# PGTNX08_pitch_out.net
KiCad netlist of a schematic drawn in EAGLE
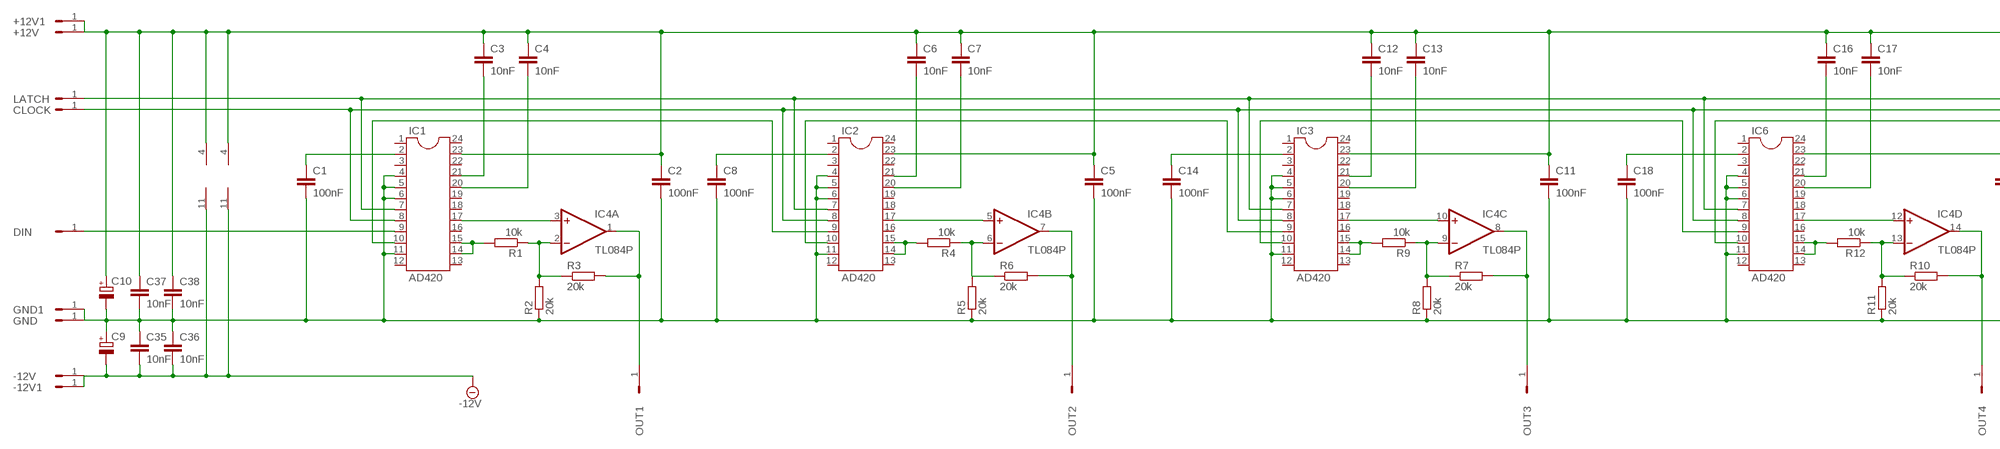
[diagram p0: schematic, sheet 1, part 1 of 2]
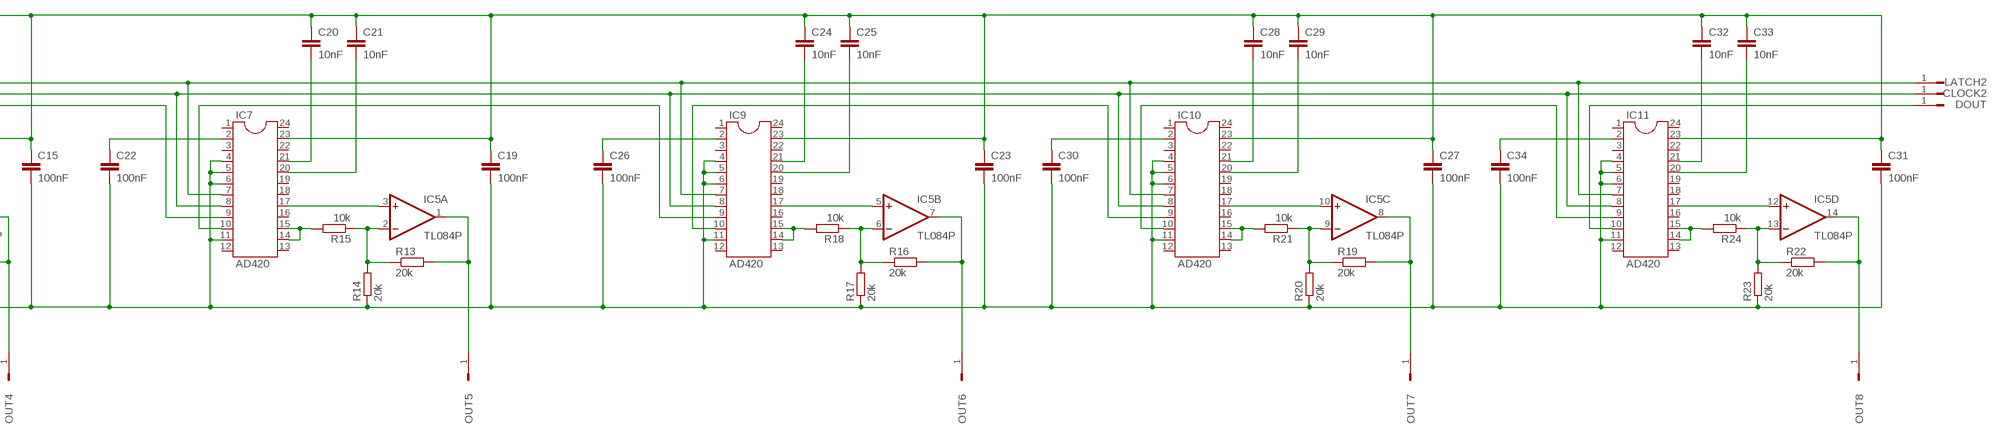
[diagram p1: schematic, sheet 1, part 2 of 2]

(export (version "E")
  (design (tool "Eeschema 10.0.6"))
  (components
    (comp (ref "+12V")
      (value "HEADER/MALE/01")
      (footprint "eagle-import:HEADER_MALE_01")
      (libsource (lib "eagle-import") (part "HEADER/MALE/01"))
    )
    (comp (ref "+12V1")
      (value "HEADER/MALE/01")
      (footprint "eagle-import:HEADER_MALE_01")
      (libsource (lib "eagle-import") (part "HEADER/MALE/01"))
    )
    (comp (ref "-12V")
      (value "HEADER/MALE/01")
      (footprint "eagle-import:HEADER_MALE_01")
      (libsource (lib "eagle-import") (part "HEADER/MALE/01"))
    )
    (comp (ref "-12V1")
      (value "HEADER/MALE/01")
      (footprint "eagle-import:HEADER_MALE_01")
      (libsource (lib "eagle-import") (part "HEADER/MALE/01"))
    )
    (comp (ref "C1")
      (value "100nF")
      (footprint "eagle-import:CERAMICDISC_5")
      (libsource (lib "eagle-import") (part "CAPACITORCERAMICDISC/5"))
    )
    (comp (ref "C2")
      (value "100nF")
      (footprint "eagle-import:CERAMICDISC_5")
      (libsource (lib "eagle-import") (part "CAPACITORCERAMICDISC/5"))
    )
    (comp (ref "C3")
      (value "10nF")
      (footprint "eagle-import:CERAMICDISC_5")
      (libsource (lib "eagle-import") (part "CAPACITORCERAMICDISC/5"))
    )
    (comp (ref "C4")
      (value "10nF")
      (footprint "eagle-import:CERAMICDISC_5")
      (libsource (lib "eagle-import") (part "CAPACITORCERAMICDISC/5"))
    )
    (comp (ref "C5")
      (value "100nF")
      (footprint "eagle-import:CERAMICDISC_5")
      (libsource (lib "eagle-import") (part "CAPACITORCERAMICDISC/5"))
    )
    (comp (ref "C6")
      (value "10nF")
      (footprint "eagle-import:CERAMICDISC_5")
      (libsource (lib "eagle-import") (part "CAPACITORCERAMICDISC/5"))
    )
    (comp (ref "C7")
      (value "10nF")
      (footprint "eagle-import:CERAMICDISC_5")
      (libsource (lib "eagle-import") (part "CAPACITORCERAMICDISC/5"))
    )
    (comp (ref "C8")
      (value "100nF")
      (footprint "eagle-import:CERAMICDISC_5")
      (libsource (lib "eagle-import") (part "CAPACITORCERAMICDISC/5"))
    )
    (comp (ref "C9")
      (value "CAPACITOR/POLARIZEDE2.5-6")
      (footprint "eagle-import:E2,5-6")
      (libsource (lib "eagle-import") (part "CAPACITOR/POLARIZEDE2.5-6"))
    )
    (comp (ref "C10")
      (value "CAPACITOR/POLARIZEDE2.5-6")
      (footprint "eagle-import:E2,5-6")
      (libsource (lib "eagle-import") (part "CAPACITOR/POLARIZEDE2.5-6"))
    )
    (comp (ref "C11")
      (value "100nF")
      (footprint "eagle-import:CERAMICDISC_5")
      (libsource (lib "eagle-import") (part "CAPACITORCERAMICDISC/5"))
    )
    (comp (ref "C12")
      (value "10nF")
      (footprint "eagle-import:CERAMICDISC_5")
      (libsource (lib "eagle-import") (part "CAPACITORCERAMICDISC/5"))
    )
    (comp (ref "C13")
      (value "10nF")
      (footprint "eagle-import:CERAMICDISC_5")
      (libsource (lib "eagle-import") (part "CAPACITORCERAMICDISC/5"))
    )
    (comp (ref "C14")
      (value "100nF")
      (footprint "eagle-import:CERAMICDISC_5")
      (libsource (lib "eagle-import") (part "CAPACITORCERAMICDISC/5"))
    )
    (comp (ref "C15")
      (value "100nF")
      (footprint "eagle-import:CERAMICDISC_5")
      (libsource (lib "eagle-import") (part "CAPACITORCERAMICDISC/5"))
    )
    (comp (ref "C16")
      (value "10nF")
      (footprint "eagle-import:CERAMICDISC_5")
      (libsource (lib "eagle-import") (part "CAPACITORCERAMICDISC/5"))
    )
    (comp (ref "C17")
      (value "10nF")
      (footprint "eagle-import:CERAMICDISC_5")
      (libsource (lib "eagle-import") (part "CAPACITORCERAMICDISC/5"))
    )
    (comp (ref "C18")
      (value "100nF")
      (footprint "eagle-import:CERAMICDISC_5")
      (libsource (lib "eagle-import") (part "CAPACITORCERAMICDISC/5"))
    )
    (comp (ref "C19")
      (value "100nF")
      (footprint "eagle-import:CERAMICDISC_5")
      (libsource (lib "eagle-import") (part "CAPACITORCERAMICDISC/5"))
    )
    (comp (ref "C20")
      (value "10nF")
      (footprint "eagle-import:CERAMICDISC_5")
      (libsource (lib "eagle-import") (part "CAPACITORCERAMICDISC/5"))
    )
    (comp (ref "C21")
      (value "10nF")
      (footprint "eagle-import:CERAMICDISC_5")
      (libsource (lib "eagle-import") (part "CAPACITORCERAMICDISC/5"))
    )
    (comp (ref "C22")
      (value "100nF")
      (footprint "eagle-import:CERAMICDISC_5")
      (libsource (lib "eagle-import") (part "CAPACITORCERAMICDISC/5"))
    )
    (comp (ref "C23")
      (value "100nF")
      (footprint "eagle-import:CERAMICDISC_5")
      (libsource (lib "eagle-import") (part "CAPACITORCERAMICDISC/5"))
    )
    (comp (ref "C24")
      (value "10nF")
      (footprint "eagle-import:CERAMICDISC_5")
      (libsource (lib "eagle-import") (part "CAPACITORCERAMICDISC/5"))
    )
    (comp (ref "C25")
      (value "10nF")
      (footprint "eagle-import:CERAMICDISC_5")
      (libsource (lib "eagle-import") (part "CAPACITORCERAMICDISC/5"))
    )
    (comp (ref "C26")
      (value "100nF")
      (footprint "eagle-import:CERAMICDISC_5")
      (libsource (lib "eagle-import") (part "CAPACITORCERAMICDISC/5"))
    )
    (comp (ref "C27")
      (value "100nF")
      (footprint "eagle-import:CERAMICDISC_5")
      (libsource (lib "eagle-import") (part "CAPACITORCERAMICDISC/5"))
    )
    (comp (ref "C28")
      (value "10nF")
      (footprint "eagle-import:CERAMICDISC_5")
      (libsource (lib "eagle-import") (part "CAPACITORCERAMICDISC/5"))
    )
    (comp (ref "C29")
      (value "10nF")
      (footprint "eagle-import:CERAMICDISC_5")
      (libsource (lib "eagle-import") (part "CAPACITORCERAMICDISC/5"))
    )
    (comp (ref "C30")
      (value "100nF")
      (footprint "eagle-import:CERAMICDISC_5")
      (libsource (lib "eagle-import") (part "CAPACITORCERAMICDISC/5"))
    )
    (comp (ref "C31")
      (value "100nF")
      (footprint "eagle-import:CERAMICDISC_5")
      (libsource (lib "eagle-import") (part "CAPACITORCERAMICDISC/5"))
    )
    (comp (ref "C32")
      (value "10nF")
      (footprint "eagle-import:CERAMICDISC_5")
      (libsource (lib "eagle-import") (part "CAPACITORCERAMICDISC/5"))
    )
    (comp (ref "C33")
      (value "10nF")
      (footprint "eagle-import:CERAMICDISC_5")
      (libsource (lib "eagle-import") (part "CAPACITORCERAMICDISC/5"))
    )
    (comp (ref "C34")
      (value "100nF")
      (footprint "eagle-import:CERAMICDISC_5")
      (libsource (lib "eagle-import") (part "CAPACITORCERAMICDISC/5"))
    )
    (comp (ref "C35")
      (value "10nF")
      (footprint "eagle-import:CERAMICDISC_5")
      (libsource (lib "eagle-import") (part "CAPACITORCERAMICDISC/5"))
    )
    (comp (ref "C36")
      (value "10nF")
      (footprint "eagle-import:CERAMICDISC_5")
      (libsource (lib "eagle-import") (part "CAPACITORCERAMICDISC/5"))
    )
    (comp (ref "C37")
      (value "10nF")
      (footprint "eagle-import:CERAMICDISC_5")
      (libsource (lib "eagle-import") (part "CAPACITORCERAMICDISC/5"))
    )
    (comp (ref "C38")
      (value "10nF")
      (footprint "eagle-import:CERAMICDISC_5")
      (libsource (lib "eagle-import") (part "CAPACITORCERAMICDISC/5"))
    )
    (comp (ref "CLOCK")
      (value "HEADER/MALE/01")
      (footprint "eagle-import:HEADER_MALE_01")
      (libsource (lib "eagle-import") (part "HEADER/MALE/01"))
    )
    (comp (ref "CLOCK2")
      (value "HEADER/MALE/01")
      (footprint "eagle-import:HEADER_MALE_01")
      (libsource (lib "eagle-import") (part "HEADER/MALE/01"))
    )
    (comp (ref "DIN")
      (value "HEADER/MALE/01")
      (footprint "eagle-import:HEADER_MALE_01")
      (libsource (lib "eagle-import") (part "HEADER/MALE/01"))
    )
    (comp (ref "DOUT")
      (value "HEADER/MALE/01")
      (footprint "eagle-import:HEADER_MALE_01")
      (libsource (lib "eagle-import") (part "HEADER/MALE/01"))
    )
    (comp (ref "GND")
      (value "HEADER/MALE/01")
      (footprint "eagle-import:HEADER_MALE_01")
      (libsource (lib "eagle-import") (part "HEADER/MALE/01"))
    )
    (comp (ref "GND1")
      (value "HEADER/MALE/01")
      (footprint "eagle-import:HEADER_MALE_01")
      (libsource (lib "eagle-import") (part "HEADER/MALE/01"))
    )
    (comp (ref "IC1")
      (value "AD420")
      (footprint "eagle-import:DIL24-3")
      (libsource (lib "eagle-import") (part "DIL24-3"))
    )
    (comp (ref "IC2")
      (value "AD420")
      (footprint "eagle-import:DIL24-3")
      (libsource (lib "eagle-import") (part "DIL24-3"))
    )
    (comp (ref "IC3")
      (value "AD420")
      (footprint "eagle-import:DIL24-3")
      (libsource (lib "eagle-import") (part "DIL24-3"))
    )
    (comp (ref "IC4")
      (value "TL084P")
      (footprint "eagle-import:DIL14")
      (libsource (lib "eagle-import") (part "TL084P"))
    )
    (comp (ref "IC5")
      (value "TL084P")
      (footprint "eagle-import:DIL14")
      (libsource (lib "eagle-import") (part "TL084P"))
    )
    (comp (ref "IC6")
      (value "AD420")
      (footprint "eagle-import:DIL24-3")
      (libsource (lib "eagle-import") (part "DIL24-3"))
    )
    (comp (ref "IC7")
      (value "AD420")
      (footprint "eagle-import:DIL24-3")
      (libsource (lib "eagle-import") (part "DIL24-3"))
    )
    (comp (ref "IC9")
      (value "AD420")
      (footprint "eagle-import:DIL24-3")
      (libsource (lib "eagle-import") (part "DIL24-3"))
    )
    (comp (ref "IC10")
      (value "AD420")
      (footprint "eagle-import:DIL24-3")
      (libsource (lib "eagle-import") (part "DIL24-3"))
    )
    (comp (ref "IC11")
      (value "AD420")
      (footprint "eagle-import:DIL24-3")
      (libsource (lib "eagle-import") (part "DIL24-3"))
    )
    (comp (ref "LATCH")
      (value "HEADER/MALE/01")
      (footprint "eagle-import:HEADER_MALE_01")
      (libsource (lib "eagle-import") (part "HEADER/MALE/01"))
    )
    (comp (ref "LATCH2")
      (value "HEADER/MALE/01")
      (footprint "eagle-import:HEADER_MALE_01")
      (libsource (lib "eagle-import") (part "HEADER/MALE/01"))
    )
    (comp (ref "OUT1")
      (value "HEADER/MALE/01")
      (footprint "eagle-import:HEADER_MALE_01")
      (libsource (lib "eagle-import") (part "HEADER/MALE/01"))
    )
    (comp (ref "OUT2")
      (value "HEADER/MALE/01")
      (footprint "eagle-import:HEADER_MALE_01")
      (libsource (lib "eagle-import") (part "HEADER/MALE/01"))
    )
    (comp (ref "OUT3")
      (value "HEADER/MALE/01")
      (footprint "eagle-import:HEADER_MALE_01")
      (libsource (lib "eagle-import") (part "HEADER/MALE/01"))
    )
    (comp (ref "OUT4")
      (value "HEADER/MALE/01")
      (footprint "eagle-import:HEADER_MALE_01")
      (libsource (lib "eagle-import") (part "HEADER/MALE/01"))
    )
    (comp (ref "OUT5")
      (value "HEADER/MALE/01")
      (footprint "eagle-import:HEADER_MALE_01")
      (libsource (lib "eagle-import") (part "HEADER/MALE/01"))
    )
    (comp (ref "OUT6")
      (value "HEADER/MALE/01")
      (footprint "eagle-import:HEADER_MALE_01")
      (libsource (lib "eagle-import") (part "HEADER/MALE/01"))
    )
    (comp (ref "OUT7")
      (value "HEADER/MALE/01")
      (footprint "eagle-import:HEADER_MALE_01")
      (libsource (lib "eagle-import") (part "HEADER/MALE/01"))
    )
    (comp (ref "OUT8")
      (value "HEADER/MALE/01")
      (footprint "eagle-import:HEADER_MALE_01")
      (libsource (lib "eagle-import") (part "HEADER/MALE/01"))
    )
    (comp (ref "R1")
      (value "10k")
      (footprint "eagle-import:0204_7")
      (libsource (lib "eagle-import") (part "R-EU_0204/7"))
    )
    (comp (ref "R2")
      (value "20k")
      (footprint "eagle-import:0204_7")
      (libsource (lib "eagle-import") (part "R-EU_0204/7"))
    )
    (comp (ref "R3")
      (value "20k")
      (footprint "eagle-import:RESISTOR_7.5")
      (libsource (lib "eagle-import") (part "RESISTORRESISTOR/UPRIGHT/7.5"))
    )
    (comp (ref "R4")
      (value "10k")
      (footprint "eagle-import:0204_7")
      (libsource (lib "eagle-import") (part "R-EU_0204/7"))
    )
    (comp (ref "R5")
      (value "20k")
      (footprint "eagle-import:0204_7")
      (libsource (lib "eagle-import") (part "R-EU_0204/7"))
    )
    (comp (ref "R6")
      (value "20k")
      (footprint "eagle-import:RESISTOR_7.5")
      (libsource (lib "eagle-import") (part "RESISTORRESISTOR/UPRIGHT/7.5"))
    )
    (comp (ref "R7")
      (value "20k")
      (footprint "eagle-import:RESISTOR_7.5")
      (libsource (lib "eagle-import") (part "RESISTORRESISTOR/UPRIGHT/7.5"))
    )
    (comp (ref "R8")
      (value "20k")
      (footprint "eagle-import:RESISTOR_7.5")
      (libsource (lib "eagle-import") (part "RESISTORRESISTOR/UPRIGHT/7.5"))
    )
    (comp (ref "R9")
      (value "10k")
      (footprint "eagle-import:RESISTOR_7.5")
      (libsource (lib "eagle-import") (part "RESISTORRESISTOR/UPRIGHT/7.5"))
    )
    (comp (ref "R10")
      (value "20k")
      (footprint "eagle-import:RESISTOR_7.5")
      (libsource (lib "eagle-import") (part "RESISTORRESISTOR/UPRIGHT/7.5"))
    )
    (comp (ref "R11")
      (value "20k")
      (footprint "eagle-import:RESISTOR_7.5")
      (libsource (lib "eagle-import") (part "RESISTORRESISTOR/UPRIGHT/7.5"))
    )
    (comp (ref "R12")
      (value "10k")
      (footprint "eagle-import:RESISTOR_7.5")
      (libsource (lib "eagle-import") (part "RESISTORRESISTOR/UPRIGHT/7.5"))
    )
    (comp (ref "R13")
      (value "20k")
      (footprint "eagle-import:RESISTOR_7.5")
      (libsource (lib "eagle-import") (part "RESISTORRESISTOR/UPRIGHT/7.5"))
    )
    (comp (ref "R14")
      (value "20k")
      (footprint "eagle-import:RESISTOR_7.5")
      (libsource (lib "eagle-import") (part "RESISTORRESISTOR/UPRIGHT/7.5"))
    )
    (comp (ref "R15")
      (value "10k")
      (footprint "eagle-import:RESISTOR_7.5")
      (libsource (lib "eagle-import") (part "RESISTORRESISTOR/UPRIGHT/7.5"))
    )
    (comp (ref "R16")
      (value "20k")
      (footprint "eagle-import:RESISTOR_7.5")
      (libsource (lib "eagle-import") (part "RESISTORRESISTOR/UPRIGHT/7.5"))
    )
    (comp (ref "R17")
      (value "20k")
      (footprint "eagle-import:RESISTOR_7.5")
      (libsource (lib "eagle-import") (part "RESISTORRESISTOR/UPRIGHT/7.5"))
    )
    (comp (ref "R18")
      (value "10k")
      (footprint "eagle-import:RESISTOR_7.5")
      (libsource (lib "eagle-import") (part "RESISTORRESISTOR/UPRIGHT/7.5"))
    )
    (comp (ref "R19")
      (value "20k")
      (footprint "eagle-import:RESISTOR_7.5")
      (libsource (lib "eagle-import") (part "RESISTORRESISTOR/UPRIGHT/7.5"))
    )
    (comp (ref "R20")
      (value "20k")
      (footprint "eagle-import:RESISTOR_7.5")
      (libsource (lib "eagle-import") (part "RESISTORRESISTOR/UPRIGHT/7.5"))
    )
    (comp (ref "R21")
      (value "10k")
      (footprint "eagle-import:RESISTOR_7.5")
      (libsource (lib "eagle-import") (part "RESISTORRESISTOR/UPRIGHT/7.5"))
    )
    (comp (ref "R22")
      (value "20k")
      (footprint "eagle-import:RESISTOR_7.5")
      (libsource (lib "eagle-import") (part "RESISTORRESISTOR/UPRIGHT/7.5"))
    )
    (comp (ref "R23")
      (value "20k")
      (footprint "eagle-import:RESISTOR_7.5")
      (libsource (lib "eagle-import") (part "RESISTORRESISTOR/UPRIGHT/7.5"))
    )
    (comp (ref "R24")
      (value "10k")
      (footprint "eagle-import:RESISTOR_7.5")
      (libsource (lib "eagle-import") (part "RESISTORRESISTOR/UPRIGHT/7.5"))
    )
  )
  (nets
    (net (code "1") (name "-12V") (class "Default")
      (node (ref "-12V") (pin "1") (pinfunction "3_1") (pintype "passive"))
      (node (ref "-12V1") (pin "1") (pinfunction "3_1") (pintype "passive"))
      (node (ref "C35") (pin "2") (pinfunction "2_2") (pintype "passive"))
      (node (ref "C36") (pin "2") (pinfunction "2_2") (pintype "passive"))
      (node (ref "C9") (pin "-") (pinfunction "-_-") (pintype "passive"))
      (node (ref "IC4") (pin "11") (pinfunction "V-_11") (pintype "power_in"))
      (node (ref "IC5") (pin "11") (pinfunction "V-_11") (pintype "power_in"))
    )
    (net (code "2") (name "Net-(+12V-3)") (class "Default")
      (node (ref "+12V") (pin "1") (pinfunction "3_1") (pintype "passive"))
      (node (ref "+12V1") (pin "1") (pinfunction "3_1") (pintype "passive"))
      (node (ref "C10") (pin "+") (pinfunction "+_+") (pintype "passive"))
      (node (ref "C11") (pin "1") (pinfunction "1_1") (pintype "passive"))
      (node (ref "C12") (pin "1") (pinfunction "1_1") (pintype "passive"))
      (node (ref "C13") (pin "1") (pinfunction "1_1") (pintype "passive"))
      (node (ref "C15") (pin "1") (pinfunction "1_1") (pintype "passive"))
      (node (ref "C16") (pin "1") (pinfunction "1_1") (pintype "passive"))
      (node (ref "C17") (pin "1") (pinfunction "1_1") (pintype "passive"))
      (node (ref "C19") (pin "1") (pinfunction "1_1") (pintype "passive"))
      (node (ref "C2") (pin "1") (pinfunction "1_1") (pintype "passive"))
      (node (ref "C20") (pin "1") (pinfunction "1_1") (pintype "passive"))
      (node (ref "C21") (pin "1") (pinfunction "1_1") (pintype "passive"))
      (node (ref "C23") (pin "1") (pinfunction "1_1") (pintype "passive"))
      (node (ref "C24") (pin "1") (pinfunction "1_1") (pintype "passive"))
      (node (ref "C25") (pin "1") (pinfunction "1_1") (pintype "passive"))
      (node (ref "C27") (pin "1") (pinfunction "1_1") (pintype "passive"))
      (node (ref "C28") (pin "1") (pinfunction "1_1") (pintype "passive"))
      (node (ref "C29") (pin "1") (pinfunction "1_1") (pintype "passive"))
      (node (ref "C3") (pin "1") (pinfunction "1_1") (pintype "passive"))
      (node (ref "C31") (pin "1") (pinfunction "1_1") (pintype "passive"))
      (node (ref "C32") (pin "1") (pinfunction "1_1") (pintype "passive"))
      (node (ref "C33") (pin "1") (pinfunction "1_1") (pintype "passive"))
      (node (ref "C37") (pin "1") (pinfunction "1_1") (pintype "passive"))
      (node (ref "C38") (pin "1") (pinfunction "1_1") (pintype "passive"))
      (node (ref "C4") (pin "1") (pinfunction "1_1") (pintype "passive"))
      (node (ref "C5") (pin "1") (pinfunction "1_1") (pintype "passive"))
      (node (ref "C6") (pin "1") (pinfunction "1_1") (pintype "passive"))
      (node (ref "C7") (pin "1") (pinfunction "1_1") (pintype "passive"))
      (node (ref "IC1") (pin "23") (pinfunction "23_23") (pintype "passive"))
      (node (ref "IC10") (pin "23") (pinfunction "23_23") (pintype "passive"))
      (node (ref "IC11") (pin "23") (pinfunction "23_23") (pintype "passive"))
      (node (ref "IC2") (pin "23") (pinfunction "23_23") (pintype "passive"))
      (node (ref "IC3") (pin "23") (pinfunction "23_23") (pintype "passive"))
      (node (ref "IC4") (pin "4") (pinfunction "V+_4") (pintype "power_in"))
      (node (ref "IC5") (pin "4") (pinfunction "V+_4") (pintype "power_in"))
      (node (ref "IC6") (pin "23") (pinfunction "23_23") (pintype "passive"))
      (node (ref "IC7") (pin "23") (pinfunction "23_23") (pintype "passive"))
      (node (ref "IC9") (pin "23") (pinfunction "23_23") (pintype "passive"))
    )
    (net (code "3") (name "Net-(C1-Pad1)") (class "Default")
      (node (ref "C1") (pin "1") (pinfunction "1_1") (pintype "passive"))
      (node (ref "IC1") (pin "2") (pinfunction "2_2") (pintype "passive"))
    )
    (net (code "4") (name "Net-(C3-Pad2)") (class "Default")
      (node (ref "C3") (pin "2") (pinfunction "2_2") (pintype "passive"))
      (node (ref "IC1") (pin "21") (pinfunction "21_21") (pintype "passive"))
    )
    (net (code "5") (name "Net-(C4-Pad2)") (class "Default")
      (node (ref "C4") (pin "2") (pinfunction "2_2") (pintype "passive"))
      (node (ref "IC1") (pin "20") (pinfunction "20_20") (pintype "passive"))
    )
    (net (code "6") (name "Net-(C6-Pad2)") (class "Default")
      (node (ref "C6") (pin "2") (pinfunction "2_2") (pintype "passive"))
      (node (ref "IC2") (pin "21") (pinfunction "21_21") (pintype "passive"))
    )
    (net (code "7") (name "Net-(C7-Pad2)") (class "Default")
      (node (ref "C7") (pin "2") (pinfunction "2_2") (pintype "passive"))
      (node (ref "IC2") (pin "20") (pinfunction "20_20") (pintype "passive"))
    )
    (net (code "8") (name "Net-(C8-Pad1)") (class "Default")
      (node (ref "C8") (pin "1") (pinfunction "1_1") (pintype "passive"))
      (node (ref "IC2") (pin "2") (pinfunction "2_2") (pintype "passive"))
    )
    (net (code "9") (name "Net-(C12-Pad2)") (class "Default")
      (node (ref "C12") (pin "2") (pinfunction "2_2") (pintype "passive"))
      (node (ref "IC3") (pin "21") (pinfunction "21_21") (pintype "passive"))
    )
    (net (code "10") (name "Net-(C13-Pad2)") (class "Default")
      (node (ref "C13") (pin "2") (pinfunction "2_2") (pintype "passive"))
      (node (ref "IC3") (pin "20") (pinfunction "20_20") (pintype "passive"))
    )
    (net (code "11") (name "Net-(C14-Pad1)") (class "Default")
      (node (ref "C14") (pin "1") (pinfunction "1_1") (pintype "passive"))
      (node (ref "IC3") (pin "2") (pinfunction "2_2") (pintype "passive"))
    )
    (net (code "12") (name "Net-(C16-Pad2)") (class "Default")
      (node (ref "C16") (pin "2") (pinfunction "2_2") (pintype "passive"))
      (node (ref "IC6") (pin "21") (pinfunction "21_21") (pintype "passive"))
    )
    (net (code "13") (name "Net-(C17-Pad2)") (class "Default")
      (node (ref "C17") (pin "2") (pinfunction "2_2") (pintype "passive"))
      (node (ref "IC6") (pin "20") (pinfunction "20_20") (pintype "passive"))
    )
    (net (code "14") (name "Net-(C18-Pad1)") (class "Default")
      (node (ref "C18") (pin "1") (pinfunction "1_1") (pintype "passive"))
      (node (ref "IC6") (pin "2") (pinfunction "2_2") (pintype "passive"))
    )
    (net (code "15") (name "Net-(C20-Pad2)") (class "Default")
      (node (ref "C20") (pin "2") (pinfunction "2_2") (pintype "passive"))
      (node (ref "IC7") (pin "21") (pinfunction "21_21") (pintype "passive"))
    )
    (net (code "16") (name "Net-(C21-Pad2)") (class "Default")
      (node (ref "C21") (pin "2") (pinfunction "2_2") (pintype "passive"))
      (node (ref "IC7") (pin "20") (pinfunction "20_20") (pintype "passive"))
    )
    (net (code "17") (name "Net-(C22-Pad1)") (class "Default")
      (node (ref "C22") (pin "1") (pinfunction "1_1") (pintype "passive"))
      (node (ref "IC7") (pin "2") (pinfunction "2_2") (pintype "passive"))
    )
    (net (code "18") (name "Net-(C24-Pad2)") (class "Default")
      (node (ref "C24") (pin "2") (pinfunction "2_2") (pintype "passive"))
      (node (ref "IC9") (pin "21") (pinfunction "21_21") (pintype "passive"))
    )
    (net (code "19") (name "Net-(C25-Pad2)") (class "Default")
      (node (ref "C25") (pin "2") (pinfunction "2_2") (pintype "passive"))
      (node (ref "IC9") (pin "20") (pinfunction "20_20") (pintype "passive"))
    )
    (net (code "20") (name "Net-(C26-Pad1)") (class "Default")
      (node (ref "C26") (pin "1") (pinfunction "1_1") (pintype "passive"))
      (node (ref "IC9") (pin "2") (pinfunction "2_2") (pintype "passive"))
    )
    (net (code "21") (name "Net-(C28-Pad2)") (class "Default")
      (node (ref "C28") (pin "2") (pinfunction "2_2") (pintype "passive"))
      (node (ref "IC10") (pin "21") (pinfunction "21_21") (pintype "passive"))
    )
    (net (code "22") (name "Net-(C29-Pad2)") (class "Default")
      (node (ref "C29") (pin "2") (pinfunction "2_2") (pintype "passive"))
      (node (ref "IC10") (pin "20") (pinfunction "20_20") (pintype "passive"))
    )
    (net (code "23") (name "Net-(C30-Pad1)") (class "Default")
      (node (ref "C30") (pin "1") (pinfunction "1_1") (pintype "passive"))
      (node (ref "IC10") (pin "2") (pinfunction "2_2") (pintype "passive"))
    )
    (net (code "24") (name "Net-(C32-Pad2)") (class "Default")
      (node (ref "C32") (pin "2") (pinfunction "2_2") (pintype "passive"))
      (node (ref "IC11") (pin "21") (pinfunction "21_21") (pintype "passive"))
    )
    (net (code "25") (name "Net-(C33-Pad2)") (class "Default")
      (node (ref "C33") (pin "2") (pinfunction "2_2") (pintype "passive"))
      (node (ref "IC11") (pin "20") (pinfunction "20_20") (pintype "passive"))
    )
    (net (code "26") (name "Net-(C34-Pad1)") (class "Default")
      (node (ref "C34") (pin "1") (pinfunction "1_1") (pintype "passive"))
      (node (ref "IC11") (pin "2") (pinfunction "2_2") (pintype "passive"))
    )
    (net (code "27") (name "Net-(CLOCK-3)") (class "Default")
      (node (ref "CLOCK") (pin "1") (pinfunction "3_1") (pintype "passive"))
      (node (ref "CLOCK2") (pin "1") (pinfunction "3_1") (pintype "passive"))
      (node (ref "IC1") (pin "8") (pinfunction "8_8") (pintype "passive"))
      (node (ref "IC10") (pin "8") (pinfunction "8_8") (pintype "passive"))
      (node (ref "IC11") (pin "8") (pinfunction "8_8") (pintype "passive"))
      (node (ref "IC2") (pin "8") (pinfunction "8_8") (pintype "passive"))
      (node (ref "IC3") (pin "8") (pinfunction "8_8") (pintype "passive"))
      (node (ref "IC6") (pin "8") (pinfunction "8_8") (pintype "passive"))
      (node (ref "IC7") (pin "8") (pinfunction "8_8") (pintype "passive"))
      (node (ref "IC9") (pin "8") (pinfunction "8_8") (pintype "passive"))
    )
    (net (code "28") (name "Net-(DIN-3)") (class "Default")
      (node (ref "DIN") (pin "1") (pinfunction "3_1") (pintype "passive"))
      (node (ref "IC1") (pin "9") (pinfunction "9_9") (pintype "passive"))
    )
    (net (code "29") (name "Net-(DOUT-3)") (class "Default")
      (node (ref "DOUT") (pin "1") (pinfunction "3_1") (pintype "passive"))
      (node (ref "IC11") (pin "10") (pinfunction "10_10") (pintype "passive"))
    )
    (net (code "30") (name "Net-(GND-3)") (class "Default")
      (node (ref "C1") (pin "2") (pinfunction "2_2") (pintype "passive"))
      (node (ref "C10") (pin "-") (pinfunction "-_-") (pintype "passive"))
      (node (ref "C11") (pin "2") (pinfunction "2_2") (pintype "passive"))
      (node (ref "C14") (pin "2") (pinfunction "2_2") (pintype "passive"))
      (node (ref "C15") (pin "2") (pinfunction "2_2") (pintype "passive"))
      (node (ref "C18") (pin "2") (pinfunction "2_2") (pintype "passive"))
      (node (ref "C19") (pin "2") (pinfunction "2_2") (pintype "passive"))
      (node (ref "C2") (pin "2") (pinfunction "2_2") (pintype "passive"))
      (node (ref "C22") (pin "2") (pinfunction "2_2") (pintype "passive"))
      (node (ref "C23") (pin "2") (pinfunction "2_2") (pintype "passive"))
      (node (ref "C26") (pin "2") (pinfunction "2_2") (pintype "passive"))
      (node (ref "C27") (pin "2") (pinfunction "2_2") (pintype "passive"))
      (node (ref "C30") (pin "2") (pinfunction "2_2") (pintype "passive"))
      (node (ref "C31") (pin "2") (pinfunction "2_2") (pintype "passive"))
      (node (ref "C34") (pin "2") (pinfunction "2_2") (pintype "passive"))
      (node (ref "C35") (pin "1") (pinfunction "1_1") (pintype "passive"))
      (node (ref "C36") (pin "1") (pinfunction "1_1") (pintype "passive"))
      (node (ref "C37") (pin "2") (pinfunction "2_2") (pintype "passive"))
      (node (ref "C38") (pin "2") (pinfunction "2_2") (pintype "passive"))
      (node (ref "C5") (pin "2") (pinfunction "2_2") (pintype "passive"))
      (node (ref "C8") (pin "2") (pinfunction "2_2") (pintype "passive"))
      (node (ref "C9") (pin "+") (pinfunction "+_+") (pintype "passive"))
      (node (ref "GND") (pin "1") (pinfunction "3_1") (pintype "passive"))
      (node (ref "GND1") (pin "1") (pinfunction "3_1") (pintype "passive"))
      (node (ref "IC1") (pin "11") (pinfunction "11_11") (pintype "passive"))
      (node (ref "IC1") (pin "4") (pinfunction "4_4") (pintype "passive"))
      (node (ref "IC1") (pin "5") (pinfunction "5_5") (pintype "passive"))
      (node (ref "IC1") (pin "6") (pinfunction "6_6") (pintype "passive"))
      (node (ref "IC10") (pin "11") (pinfunction "11_11") (pintype "passive"))
      (node (ref "IC10") (pin "4") (pinfunction "4_4") (pintype "passive"))
      (node (ref "IC10") (pin "5") (pinfunction "5_5") (pintype "passive"))
      (node (ref "IC10") (pin "6") (pinfunction "6_6") (pintype "passive"))
      (node (ref "IC11") (pin "11") (pinfunction "11_11") (pintype "passive"))
      (node (ref "IC11") (pin "4") (pinfunction "4_4") (pintype "passive"))
      (node (ref "IC11") (pin "5") (pinfunction "5_5") (pintype "passive"))
      (node (ref "IC11") (pin "6") (pinfunction "6_6") (pintype "passive"))
      (node (ref "IC2") (pin "11") (pinfunction "11_11") (pintype "passive"))
      (node (ref "IC2") (pin "4") (pinfunction "4_4") (pintype "passive"))
      (node (ref "IC2") (pin "5") (pinfunction "5_5") (pintype "passive"))
      (node (ref "IC2") (pin "6") (pinfunction "6_6") (pintype "passive"))
      (node (ref "IC3") (pin "11") (pinfunction "11_11") (pintype "passive"))
      (node (ref "IC3") (pin "4") (pinfunction "4_4") (pintype "passive"))
      (node (ref "IC3") (pin "5") (pinfunction "5_5") (pintype "passive"))
      (node (ref "IC3") (pin "6") (pinfunction "6_6") (pintype "passive"))
      (node (ref "IC6") (pin "11") (pinfunction "11_11") (pintype "passive"))
      (node (ref "IC6") (pin "4") (pinfunction "4_4") (pintype "passive"))
      (node (ref "IC6") (pin "5") (pinfunction "5_5") (pintype "passive"))
      (node (ref "IC6") (pin "6") (pinfunction "6_6") (pintype "passive"))
      (node (ref "IC7") (pin "11") (pinfunction "11_11") (pintype "passive"))
      (node (ref "IC7") (pin "4") (pinfunction "4_4") (pintype "passive"))
      (node (ref "IC7") (pin "5") (pinfunction "5_5") (pintype "passive"))
      (node (ref "IC7") (pin "6") (pinfunction "6_6") (pintype "passive"))
      (node (ref "IC9") (pin "11") (pinfunction "11_11") (pintype "passive"))
      (node (ref "IC9") (pin "4") (pinfunction "4_4") (pintype "passive"))
      (node (ref "IC9") (pin "5") (pinfunction "5_5") (pintype "passive"))
      (node (ref "IC9") (pin "6") (pinfunction "6_6") (pintype "passive"))
      (node (ref "R11") (pin "1") (pinfunction "1_1") (pintype "passive"))
      (node (ref "R14") (pin "1") (pinfunction "1_1") (pintype "passive"))
      (node (ref "R17") (pin "1") (pinfunction "1_1") (pintype "passive"))
      (node (ref "R2") (pin "1") (pinfunction "1_1") (pintype "passive"))
      (node (ref "R20") (pin "1") (pinfunction "1_1") (pintype "passive"))
      (node (ref "R23") (pin "1") (pinfunction "1_1") (pintype "passive"))
      (node (ref "R5") (pin "1") (pinfunction "1_1") (pintype "passive"))
      (node (ref "R8") (pin "1") (pinfunction "1_1") (pintype "passive"))
    )
    (net (code "31") (name "Net-(IC1-Pad10)") (class "Default")
      (node (ref "IC1") (pin "10") (pinfunction "10_10") (pintype "passive"))
      (node (ref "IC2") (pin "9") (pinfunction "9_9") (pintype "passive"))
    )
    (net (code "32") (name "Net-(IC1-Pad14)") (class "Default")
      (node (ref "IC1") (pin "14") (pinfunction "14_14") (pintype "passive"))
      (node (ref "IC1") (pin "15") (pinfunction "15_15") (pintype "passive"))
      (node (ref "R1") (pin "2") (pinfunction "2_2") (pintype "passive"))
    )
    (net (code "33") (name "Net-(IC2-Pad10)") (class "Default")
      (node (ref "IC2") (pin "10") (pinfunction "10_10") (pintype "passive"))
      (node (ref "IC3") (pin "9") (pinfunction "9_9") (pintype "passive"))
    )
    (net (code "34") (name "Net-(IC2-Pad14)") (class "Default")
      (node (ref "IC2") (pin "14") (pinfunction "14_14") (pintype "passive"))
      (node (ref "IC2") (pin "15") (pinfunction "15_15") (pintype "passive"))
      (node (ref "R4") (pin "2") (pinfunction "2_2") (pintype "passive"))
    )
    (net (code "35") (name "Net-(IC3-Pad10)") (class "Default")
      (node (ref "IC3") (pin "10") (pinfunction "10_10") (pintype "passive"))
      (node (ref "IC6") (pin "9") (pinfunction "9_9") (pintype "passive"))
    )
    (net (code "36") (name "Net-(IC3-Pad14)") (class "Default")
      (node (ref "IC3") (pin "14") (pinfunction "14_14") (pintype "passive"))
      (node (ref "IC3") (pin "15") (pinfunction "15_15") (pintype "passive"))
      (node (ref "R9") (pin "2") (pinfunction "2_2") (pintype "passive"))
    )
    (net (code "37") (name "Net-(IC4A-+IN)") (class "Default")
      (node (ref "IC1") (pin "17") (pinfunction "17_17") (pintype "passive"))
      (node (ref "IC4") (pin "3") (pinfunction "+IN_3") (pintype "input"))
    )
    (net (code "38") (name "Net-(IC4A--IN)") (class "Default")
      (node (ref "IC4") (pin "2") (pinfunction "-IN_2") (pintype "input"))
      (node (ref "R1") (pin "1") (pinfunction "1_1") (pintype "passive"))
      (node (ref "R2") (pin "2") (pinfunction "2_2") (pintype "passive"))
      (node (ref "R3") (pin "1") (pinfunction "1_1") (pintype "passive"))
    )
    (net (code "39") (name "Net-(IC4A-OUT)") (class "Default")
      (node (ref "IC4") (pin "1") (pinfunction "OUT_1") (pintype "output"))
      (node (ref "OUT1") (pin "1") (pinfunction "3_1") (pintype "passive"))
      (node (ref "R3") (pin "2") (pinfunction "2_2") (pintype "passive"))
    )
    (net (code "40") (name "Net-(IC4B-+IN)") (class "Default")
      (node (ref "IC2") (pin "17") (pinfunction "17_17") (pintype "passive"))
      (node (ref "IC4") (pin "5") (pinfunction "+IN_5") (pintype "input"))
    )
    (net (code "41") (name "Net-(IC4B--IN)") (class "Default")
      (node (ref "IC4") (pin "6") (pinfunction "-IN_6") (pintype "input"))
      (node (ref "R4") (pin "1") (pinfunction "1_1") (pintype "passive"))
      (node (ref "R5") (pin "2") (pinfunction "2_2") (pintype "passive"))
      (node (ref "R6") (pin "1") (pinfunction "1_1") (pintype "passive"))
    )
    (net (code "42") (name "Net-(IC4B-OUT)") (class "Default")
      (node (ref "IC4") (pin "7") (pinfunction "OUT_7") (pintype "output"))
      (node (ref "OUT2") (pin "1") (pinfunction "3_1") (pintype "passive"))
      (node (ref "R6") (pin "2") (pinfunction "2_2") (pintype "passive"))
    )
    (net (code "43") (name "Net-(IC4C-+IN)") (class "Default")
      (node (ref "IC3") (pin "17") (pinfunction "17_17") (pintype "passive"))
      (node (ref "IC4") (pin "10") (pinfunction "+IN_10") (pintype "input"))
    )
    (net (code "44") (name "Net-(IC4C--IN)") (class "Default")
      (node (ref "IC4") (pin "9") (pinfunction "-IN_9") (pintype "input"))
      (node (ref "R7") (pin "1") (pinfunction "1_1") (pintype "passive"))
      (node (ref "R8") (pin "2") (pinfunction "2_2") (pintype "passive"))
      (node (ref "R9") (pin "1") (pinfunction "1_1") (pintype "passive"))
    )
    (net (code "45") (name "Net-(IC4C-OUT)") (class "Default")
      (node (ref "IC4") (pin "8") (pinfunction "OUT_8") (pintype "output"))
      (node (ref "OUT3") (pin "1") (pinfunction "3_1") (pintype "passive"))
      (node (ref "R7") (pin "2") (pinfunction "2_2") (pintype "passive"))
    )
    (net (code "46") (name "Net-(IC4D-+IN)") (class "Default")
      (node (ref "IC4") (pin "12") (pinfunction "+IN_12") (pintype "input"))
      (node (ref "IC6") (pin "17") (pinfunction "17_17") (pintype "passive"))
    )
    (net (code "47") (name "Net-(IC4D--IN)") (class "Default")
      (node (ref "IC4") (pin "13") (pinfunction "-IN_13") (pintype "input"))
      (node (ref "R10") (pin "1") (pinfunction "1_1") (pintype "passive"))
      (node (ref "R11") (pin "2") (pinfunction "2_2") (pintype "passive"))
      (node (ref "R12") (pin "1") (pinfunction "1_1") (pintype "passive"))
    )
    (net (code "48") (name "Net-(IC4D-OUT)") (class "Default")
      (node (ref "IC4") (pin "14") (pinfunction "OUT_14") (pintype "output"))
      (node (ref "OUT4") (pin "1") (pinfunction "3_1") (pintype "passive"))
      (node (ref "R10") (pin "2") (pinfunction "2_2") (pintype "passive"))
    )
    (net (code "49") (name "Net-(IC5A-+IN)") (class "Default")
      (node (ref "IC5") (pin "3") (pinfunction "+IN_3") (pintype "input"))
      (node (ref "IC7") (pin "17") (pinfunction "17_17") (pintype "passive"))
    )
    (net (code "50") (name "Net-(IC5A--IN)") (class "Default")
      (node (ref "IC5") (pin "2") (pinfunction "-IN_2") (pintype "input"))
      (node (ref "R13") (pin "1") (pinfunction "1_1") (pintype "passive"))
      (node (ref "R14") (pin "2") (pinfunction "2_2") (pintype "passive"))
      (node (ref "R15") (pin "1") (pinfunction "1_1") (pintype "passive"))
    )
    (net (code "51") (name "Net-(IC5A-OUT)") (class "Default")
      (node (ref "IC5") (pin "1") (pinfunction "OUT_1") (pintype "output"))
      (node (ref "OUT5") (pin "1") (pinfunction "3_1") (pintype "passive"))
      (node (ref "R13") (pin "2") (pinfunction "2_2") (pintype "passive"))
    )
    (net (code "52") (name "Net-(IC5B-+IN)") (class "Default")
      (node (ref "IC5") (pin "5") (pinfunction "+IN_5") (pintype "input"))
      (node (ref "IC9") (pin "17") (pinfunction "17_17") (pintype "passive"))
    )
    (net (code "53") (name "Net-(IC5B--IN)") (class "Default")
      (node (ref "IC5") (pin "6") (pinfunction "-IN_6") (pintype "input"))
      (node (ref "R16") (pin "1") (pinfunction "1_1") (pintype "passive"))
      (node (ref "R17") (pin "2") (pinfunction "2_2") (pintype "passive"))
      (node (ref "R18") (pin "1") (pinfunction "1_1") (pintype "passive"))
    )
    (net (code "54") (name "Net-(IC5B-OUT)") (class "Default")
      (node (ref "IC5") (pin "7") (pinfunction "OUT_7") (pintype "output"))
      (node (ref "OUT6") (pin "1") (pinfunction "3_1") (pintype "passive"))
      (node (ref "R16") (pin "2") (pinfunction "2_2") (pintype "passive"))
    )
    (net (code "55") (name "Net-(IC5C-+IN)") (class "Default")
      (node (ref "IC10") (pin "17") (pinfunction "17_17") (pintype "passive"))
      (node (ref "IC5") (pin "10") (pinfunction "+IN_10") (pintype "input"))
    )
    (net (code "56") (name "Net-(IC5C--IN)") (class "Default")
      (node (ref "IC5") (pin "9") (pinfunction "-IN_9") (pintype "input"))
      (node (ref "R19") (pin "1") (pinfunction "1_1") (pintype "passive"))
      (node (ref "R20") (pin "2") (pinfunction "2_2") (pintype "passive"))
      (node (ref "R21") (pin "1") (pinfunction "1_1") (pintype "passive"))
    )
    (net (code "57") (name "Net-(IC5C-OUT)") (class "Default")
      (node (ref "IC5") (pin "8") (pinfunction "OUT_8") (pintype "output"))
      (node (ref "OUT7") (pin "1") (pinfunction "3_1") (pintype "passive"))
      (node (ref "R19") (pin "2") (pinfunction "2_2") (pintype "passive"))
    )
    (net (code "58") (name "Net-(IC5D-+IN)") (class "Default")
      (node (ref "IC11") (pin "17") (pinfunction "17_17") (pintype "passive"))
      (node (ref "IC5") (pin "12") (pinfunction "+IN_12") (pintype "input"))
    )
    (net (code "59") (name "Net-(IC5D--IN)") (class "Default")
      (node (ref "IC5") (pin "13") (pinfunction "-IN_13") (pintype "input"))
      (node (ref "R22") (pin "1") (pinfunction "1_1") (pintype "passive"))
      (node (ref "R23") (pin "2") (pinfunction "2_2") (pintype "passive"))
      (node (ref "R24") (pin "1") (pinfunction "1_1") (pintype "passive"))
    )
    (net (code "60") (name "Net-(IC5D-OUT)") (class "Default")
      (node (ref "IC5") (pin "14") (pinfunction "OUT_14") (pintype "output"))
      (node (ref "OUT8") (pin "1") (pinfunction "3_1") (pintype "passive"))
      (node (ref "R22") (pin "2") (pinfunction "2_2") (pintype "passive"))
    )
    (net (code "61") (name "Net-(IC6-Pad10)") (class "Default")
      (node (ref "IC6") (pin "10") (pinfunction "10_10") (pintype "passive"))
      (node (ref "IC7") (pin "9") (pinfunction "9_9") (pintype "passive"))
    )
    (net (code "62") (name "Net-(IC6-Pad14)") (class "Default")
      (node (ref "IC6") (pin "14") (pinfunction "14_14") (pintype "passive"))
      (node (ref "IC6") (pin "15") (pinfunction "15_15") (pintype "passive"))
      (node (ref "R12") (pin "2") (pinfunction "2_2") (pintype "passive"))
    )
    (net (code "63") (name "Net-(IC7-Pad10)") (class "Default")
      (node (ref "IC7") (pin "10") (pinfunction "10_10") (pintype "passive"))
      (node (ref "IC9") (pin "9") (pinfunction "9_9") (pintype "passive"))
    )
    (net (code "64") (name "Net-(IC7-Pad14)") (class "Default")
      (node (ref "IC7") (pin "14") (pinfunction "14_14") (pintype "passive"))
      (node (ref "IC7") (pin "15") (pinfunction "15_15") (pintype "passive"))
      (node (ref "R15") (pin "2") (pinfunction "2_2") (pintype "passive"))
    )
    (net (code "65") (name "Net-(IC9-Pad14)") (class "Default")
      (node (ref "IC9") (pin "14") (pinfunction "14_14") (pintype "passive"))
      (node (ref "IC9") (pin "15") (pinfunction "15_15") (pintype "passive"))
      (node (ref "R18") (pin "2") (pinfunction "2_2") (pintype "passive"))
    )
    (net (code "66") (name "Net-(IC10-Pad9)") (class "Default")
      (node (ref "IC10") (pin "9") (pinfunction "9_9") (pintype "passive"))
      (node (ref "IC9") (pin "10") (pinfunction "10_10") (pintype "passive"))
    )
    (net (code "67") (name "Net-(IC10-Pad10)") (class "Default")
      (node (ref "IC10") (pin "10") (pinfunction "10_10") (pintype "passive"))
      (node (ref "IC11") (pin "9") (pinfunction "9_9") (pintype "passive"))
    )
    (net (code "68") (name "Net-(IC10-Pad14)") (class "Default")
      (node (ref "IC10") (pin "14") (pinfunction "14_14") (pintype "passive"))
      (node (ref "IC10") (pin "15") (pinfunction "15_15") (pintype "passive"))
      (node (ref "R21") (pin "2") (pinfunction "2_2") (pintype "passive"))
    )
    (net (code "69") (name "Net-(IC11-Pad14)") (class "Default")
      (node (ref "IC11") (pin "14") (pinfunction "14_14") (pintype "passive"))
      (node (ref "IC11") (pin "15") (pinfunction "15_15") (pintype "passive"))
      (node (ref "R24") (pin "2") (pinfunction "2_2") (pintype "passive"))
    )
    (net (code "70") (name "Net-(LATCH-3)") (class "Default")
      (node (ref "IC1") (pin "7") (pinfunction "7_7") (pintype "passive"))
      (node (ref "IC10") (pin "7") (pinfunction "7_7") (pintype "passive"))
      (node (ref "IC11") (pin "7") (pinfunction "7_7") (pintype "passive"))
      (node (ref "IC2") (pin "7") (pinfunction "7_7") (pintype "passive"))
      (node (ref "IC3") (pin "7") (pinfunction "7_7") (pintype "passive"))
      (node (ref "IC6") (pin "7") (pinfunction "7_7") (pintype "passive"))
      (node (ref "IC7") (pin "7") (pinfunction "7_7") (pintype "passive"))
      (node (ref "IC9") (pin "7") (pinfunction "7_7") (pintype "passive"))
      (node (ref "LATCH") (pin "1") (pinfunction "3_1") (pintype "passive"))
      (node (ref "LATCH2") (pin "1") (pinfunction "3_1") (pintype "passive"))
    )
    (net (code "71") (name "unconnected-(IC1-Pad1)") (class "Default")
      (node (ref "IC1") (pin "1") (pinfunction "1_1") (pintype "passive"))
    )
    (net (code "72") (name "unconnected-(IC1-Pad3)") (class "Default")
      (node (ref "IC1") (pin "3") (pinfunction "3_3") (pintype "passive"))
    )
    (net (code "73") (name "unconnected-(IC1-Pad12)") (class "Default")
      (node (ref "IC1") (pin "12") (pinfunction "12_12") (pintype "passive"))
    )
    (net (code "74") (name "unconnected-(IC1-Pad13)") (class "Default")
      (node (ref "IC1") (pin "13") (pinfunction "13_13") (pintype "passive"))
    )
    (net (code "75") (name "unconnected-(IC1-Pad16)") (class "Default")
      (node (ref "IC1") (pin "16") (pinfunction "16_16") (pintype "passive"))
    )
    (net (code "76") (name "unconnected-(IC1-Pad18)") (class "Default")
      (node (ref "IC1") (pin "18") (pinfunction "18_18") (pintype "passive"))
    )
    (net (code "77") (name "unconnected-(IC1-Pad19)") (class "Default")
      (node (ref "IC1") (pin "19") (pinfunction "19_19") (pintype "passive"))
    )
    (net (code "78") (name "unconnected-(IC1-Pad22)") (class "Default")
      (node (ref "IC1") (pin "22") (pinfunction "22_22") (pintype "passive"))
    )
    (net (code "79") (name "unconnected-(IC1-Pad24)") (class "Default")
      (node (ref "IC1") (pin "24") (pinfunction "24_24") (pintype "passive"))
    )
    (net (code "80") (name "unconnected-(IC2-Pad1)") (class "Default")
      (node (ref "IC2") (pin "1") (pinfunction "1_1") (pintype "passive"))
    )
    (net (code "81") (name "unconnected-(IC2-Pad3)") (class "Default")
      (node (ref "IC2") (pin "3") (pinfunction "3_3") (pintype "passive"))
    )
    (net (code "82") (name "unconnected-(IC2-Pad12)") (class "Default")
      (node (ref "IC2") (pin "12") (pinfunction "12_12") (pintype "passive"))
    )
    (net (code "83") (name "unconnected-(IC2-Pad13)") (class "Default")
      (node (ref "IC2") (pin "13") (pinfunction "13_13") (pintype "passive"))
    )
    (net (code "84") (name "unconnected-(IC2-Pad16)") (class "Default")
      (node (ref "IC2") (pin "16") (pinfunction "16_16") (pintype "passive"))
    )
    (net (code "85") (name "unconnected-(IC2-Pad18)") (class "Default")
      (node (ref "IC2") (pin "18") (pinfunction "18_18") (pintype "passive"))
    )
    (net (code "86") (name "unconnected-(IC2-Pad19)") (class "Default")
      (node (ref "IC2") (pin "19") (pinfunction "19_19") (pintype "passive"))
    )
    (net (code "87") (name "unconnected-(IC2-Pad22)") (class "Default")
      (node (ref "IC2") (pin "22") (pinfunction "22_22") (pintype "passive"))
    )
    (net (code "88") (name "unconnected-(IC2-Pad24)") (class "Default")
      (node (ref "IC2") (pin "24") (pinfunction "24_24") (pintype "passive"))
    )
    (net (code "89") (name "unconnected-(IC3-Pad1)") (class "Default")
      (node (ref "IC3") (pin "1") (pinfunction "1_1") (pintype "passive"))
    )
    (net (code "90") (name "unconnected-(IC3-Pad3)") (class "Default")
      (node (ref "IC3") (pin "3") (pinfunction "3_3") (pintype "passive"))
    )
    (net (code "91") (name "unconnected-(IC3-Pad12)") (class "Default")
      (node (ref "IC3") (pin "12") (pinfunction "12_12") (pintype "passive"))
    )
    (net (code "92") (name "unconnected-(IC3-Pad13)") (class "Default")
      (node (ref "IC3") (pin "13") (pinfunction "13_13") (pintype "passive"))
    )
    (net (code "93") (name "unconnected-(IC3-Pad16)") (class "Default")
      (node (ref "IC3") (pin "16") (pinfunction "16_16") (pintype "passive"))
    )
    (net (code "94") (name "unconnected-(IC3-Pad18)") (class "Default")
      (node (ref "IC3") (pin "18") (pinfunction "18_18") (pintype "passive"))
    )
    (net (code "95") (name "unconnected-(IC3-Pad19)") (class "Default")
      (node (ref "IC3") (pin "19") (pinfunction "19_19") (pintype "passive"))
    )
    (net (code "96") (name "unconnected-(IC3-Pad22)") (class "Default")
      (node (ref "IC3") (pin "22") (pinfunction "22_22") (pintype "passive"))
    )
    (net (code "97") (name "unconnected-(IC3-Pad24)") (class "Default")
      (node (ref "IC3") (pin "24") (pinfunction "24_24") (pintype "passive"))
    )
    (net (code "98") (name "unconnected-(IC6-Pad1)") (class "Default")
      (node (ref "IC6") (pin "1") (pinfunction "1_1") (pintype "passive"))
    )
    (net (code "99") (name "unconnected-(IC6-Pad3)") (class "Default")
      (node (ref "IC6") (pin "3") (pinfunction "3_3") (pintype "passive"))
    )
    (net (code "100") (name "unconnected-(IC6-Pad12)") (class "Default")
      (node (ref "IC6") (pin "12") (pinfunction "12_12") (pintype "passive"))
    )
    (net (code "101") (name "unconnected-(IC6-Pad13)") (class "Default")
      (node (ref "IC6") (pin "13") (pinfunction "13_13") (pintype "passive"))
    )
    (net (code "102") (name "unconnected-(IC6-Pad16)") (class "Default")
      (node (ref "IC6") (pin "16") (pinfunction "16_16") (pintype "passive"))
    )
    (net (code "103") (name "unconnected-(IC6-Pad18)") (class "Default")
      (node (ref "IC6") (pin "18") (pinfunction "18_18") (pintype "passive"))
    )
    (net (code "104") (name "unconnected-(IC6-Pad19)") (class "Default")
      (node (ref "IC6") (pin "19") (pinfunction "19_19") (pintype "passive"))
    )
    (net (code "105") (name "unconnected-(IC6-Pad22)") (class "Default")
      (node (ref "IC6") (pin "22") (pinfunction "22_22") (pintype "passive"))
    )
    (net (code "106") (name "unconnected-(IC6-Pad24)") (class "Default")
      (node (ref "IC6") (pin "24") (pinfunction "24_24") (pintype "passive"))
    )
    (net (code "107") (name "unconnected-(IC7-Pad1)") (class "Default")
      (node (ref "IC7") (pin "1") (pinfunction "1_1") (pintype "passive"))
    )
    (net (code "108") (name "unconnected-(IC7-Pad3)") (class "Default")
      (node (ref "IC7") (pin "3") (pinfunction "3_3") (pintype "passive"))
    )
    (net (code "109") (name "unconnected-(IC7-Pad12)") (class "Default")
      (node (ref "IC7") (pin "12") (pinfunction "12_12") (pintype "passive"))
    )
    (net (code "110") (name "unconnected-(IC7-Pad13)") (class "Default")
      (node (ref "IC7") (pin "13") (pinfunction "13_13") (pintype "passive"))
    )
    (net (code "111") (name "unconnected-(IC7-Pad16)") (class "Default")
      (node (ref "IC7") (pin "16") (pinfunction "16_16") (pintype "passive"))
    )
    (net (code "112") (name "unconnected-(IC7-Pad18)") (class "Default")
      (node (ref "IC7") (pin "18") (pinfunction "18_18") (pintype "passive"))
    )
    (net (code "113") (name "unconnected-(IC7-Pad19)") (class "Default")
      (node (ref "IC7") (pin "19") (pinfunction "19_19") (pintype "passive"))
    )
    (net (code "114") (name "unconnected-(IC7-Pad22)") (class "Default")
      (node (ref "IC7") (pin "22") (pinfunction "22_22") (pintype "passive"))
    )
    (net (code "115") (name "unconnected-(IC7-Pad24)") (class "Default")
      (node (ref "IC7") (pin "24") (pinfunction "24_24") (pintype "passive"))
    )
    (net (code "116") (name "unconnected-(IC9-Pad1)") (class "Default")
      (node (ref "IC9") (pin "1") (pinfunction "1_1") (pintype "passive"))
    )
    (net (code "117") (name "unconnected-(IC9-Pad3)") (class "Default")
      (node (ref "IC9") (pin "3") (pinfunction "3_3") (pintype "passive"))
    )
    (net (code "118") (name "unconnected-(IC9-Pad12)") (class "Default")
      (node (ref "IC9") (pin "12") (pinfunction "12_12") (pintype "passive"))
    )
    (net (code "119") (name "unconnected-(IC9-Pad13)") (class "Default")
      (node (ref "IC9") (pin "13") (pinfunction "13_13") (pintype "passive"))
    )
    (net (code "120") (name "unconnected-(IC9-Pad16)") (class "Default")
      (node (ref "IC9") (pin "16") (pinfunction "16_16") (pintype "passive"))
    )
    (net (code "121") (name "unconnected-(IC9-Pad18)") (class "Default")
      (node (ref "IC9") (pin "18") (pinfunction "18_18") (pintype "passive"))
    )
    (net (code "122") (name "unconnected-(IC9-Pad19)") (class "Default")
      (node (ref "IC9") (pin "19") (pinfunction "19_19") (pintype "passive"))
    )
    (net (code "123") (name "unconnected-(IC9-Pad22)") (class "Default")
      (node (ref "IC9") (pin "22") (pinfunction "22_22") (pintype "passive"))
    )
    (net (code "124") (name "unconnected-(IC9-Pad24)") (class "Default")
      (node (ref "IC9") (pin "24") (pinfunction "24_24") (pintype "passive"))
    )
    (net (code "125") (name "unconnected-(IC10-Pad1)") (class "Default")
      (node (ref "IC10") (pin "1") (pinfunction "1_1") (pintype "passive"))
    )
    (net (code "126") (name "unconnected-(IC10-Pad3)") (class "Default")
      (node (ref "IC10") (pin "3") (pinfunction "3_3") (pintype "passive"))
    )
    (net (code "127") (name "unconnected-(IC10-Pad12)") (class "Default")
      (node (ref "IC10") (pin "12") (pinfunction "12_12") (pintype "passive"))
    )
    (net (code "128") (name "unconnected-(IC10-Pad13)") (class "Default")
      (node (ref "IC10") (pin "13") (pinfunction "13_13") (pintype "passive"))
    )
    (net (code "129") (name "unconnected-(IC10-Pad16)") (class "Default")
      (node (ref "IC10") (pin "16") (pinfunction "16_16") (pintype "passive"))
    )
    (net (code "130") (name "unconnected-(IC10-Pad18)") (class "Default")
      (node (ref "IC10") (pin "18") (pinfunction "18_18") (pintype "passive"))
    )
    (net (code "131") (name "unconnected-(IC10-Pad19)") (class "Default")
      (node (ref "IC10") (pin "19") (pinfunction "19_19") (pintype "passive"))
    )
    (net (code "132") (name "unconnected-(IC10-Pad22)") (class "Default")
      (node (ref "IC10") (pin "22") (pinfunction "22_22") (pintype "passive"))
    )
    (net (code "133") (name "unconnected-(IC10-Pad24)") (class "Default")
      (node (ref "IC10") (pin "24") (pinfunction "24_24") (pintype "passive"))
    )
    (net (code "134") (name "unconnected-(IC11-Pad1)") (class "Default")
      (node (ref "IC11") (pin "1") (pinfunction "1_1") (pintype "passive"))
    )
    (net (code "135") (name "unconnected-(IC11-Pad3)") (class "Default")
      (node (ref "IC11") (pin "3") (pinfunction "3_3") (pintype "passive"))
    )
    (net (code "136") (name "unconnected-(IC11-Pad12)") (class "Default")
      (node (ref "IC11") (pin "12") (pinfunction "12_12") (pintype "passive"))
    )
    (net (code "137") (name "unconnected-(IC11-Pad13)") (class "Default")
      (node (ref "IC11") (pin "13") (pinfunction "13_13") (pintype "passive"))
    )
    (net (code "138") (name "unconnected-(IC11-Pad16)") (class "Default")
      (node (ref "IC11") (pin "16") (pinfunction "16_16") (pintype "passive"))
    )
    (net (code "139") (name "unconnected-(IC11-Pad18)") (class "Default")
      (node (ref "IC11") (pin "18") (pinfunction "18_18") (pintype "passive"))
    )
    (net (code "140") (name "unconnected-(IC11-Pad19)") (class "Default")
      (node (ref "IC11") (pin "19") (pinfunction "19_19") (pintype "passive"))
    )
    (net (code "141") (name "unconnected-(IC11-Pad22)") (class "Default")
      (node (ref "IC11") (pin "22") (pinfunction "22_22") (pintype "passive"))
    )
    (net (code "142") (name "unconnected-(IC11-Pad24)") (class "Default")
      (node (ref "IC11") (pin "24") (pinfunction "24_24") (pintype "passive"))
    )
  )
)
